# battery_buzzer.net
KiCad netlist of a schematic drawn in EAGLE
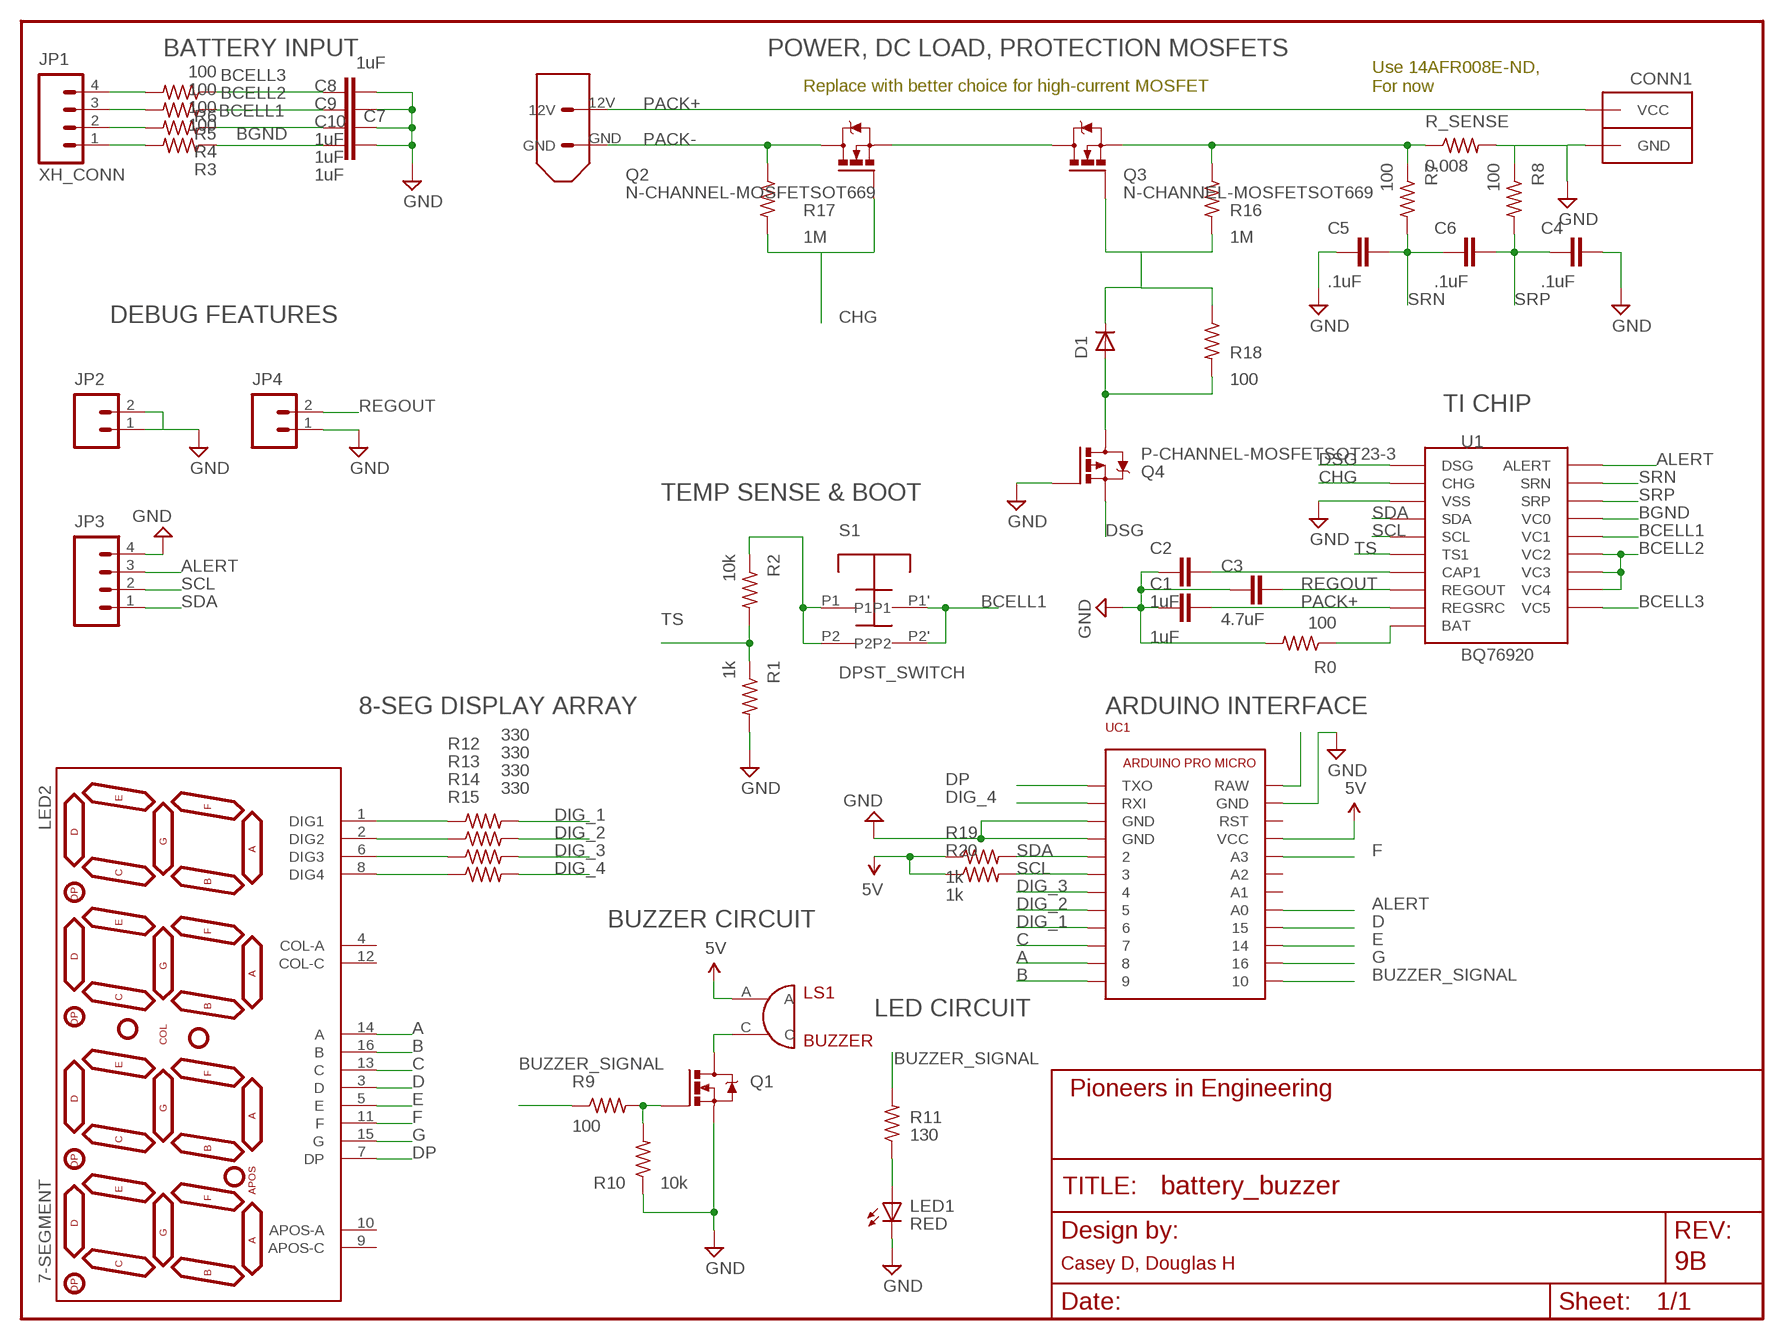
[diagram p0: schematic, sheet 1]

(export (version "E")
  (design (tool "Eeschema 10.0.6"))
  (components
    (comp (ref "C1")
      (value "1uF")
      (footprint "eagle-import:0603-CAP")
      (libsource (lib "eagle-import") (part "CAP0603-CAP"))
    )
    (comp (ref "C2")
      (value "1uF")
      (footprint "eagle-import:0603-CAP")
      (libsource (lib "eagle-import") (part "CAP0603-CAP"))
    )
    (comp (ref "C3")
      (value "4.7uF")
      (footprint "eagle-import:0603-CAP")
      (libsource (lib "eagle-import") (part "CAP0603-CAP"))
    )
    (comp (ref "C4")
      (value ".1uF")
      (footprint "eagle-import:0603-CAP")
      (libsource (lib "eagle-import") (part "CAP0603-CAP"))
    )
    (comp (ref "C5")
      (value ".1uF")
      (footprint "eagle-import:0603-CAP")
      (libsource (lib "eagle-import") (part "CAP0603-CAP"))
    )
    (comp (ref "C6")
      (value ".1uF")
      (footprint "eagle-import:0603-CAP")
      (libsource (lib "eagle-import") (part "CAP0603-CAP"))
    )
    (comp (ref "C7")
      (value "1uF")
      (footprint "eagle-import:0603-CAP")
      (libsource (lib "eagle-import") (part "CAP0603-CAP"))
    )
    (comp (ref "C8")
      (value "1uF")
      (footprint "eagle-import:0603-CAP")
      (libsource (lib "eagle-import") (part "CAP0603-CAP"))
    )
    (comp (ref "C9")
      (value "1uF")
      (footprint "eagle-import:0603-CAP")
      (libsource (lib "eagle-import") (part "CAP0603-CAP"))
    )
    (comp (ref "C10")
      (value "1uF")
      (footprint "eagle-import:0603-CAP")
      (libsource (lib "eagle-import") (part "CAP0603-CAP"))
    )
    (comp (ref "CONN1")
      (value "ANDERSONVERTICAL")
      (footprint "eagle-import:ANDERSON_VERTICAL")
      (libsource (lib "eagle-import") (part "ANDERSONVERTICAL"))
    )
    (comp (ref "D1")
      (value "DIODESOD-323")
      (footprint "eagle-import:SOD-323")
      (libsource (lib "eagle-import") (part "DIODESOD-323"))
    )
    (comp (ref "JP1")
      (value "XH_CONN")
      (footprint "eagle-import:XH_CONNECTOR_4POS_2.5MM")
      (libsource (lib "eagle-import") (part "XH_CONNECTOR_4POS"))
    )
    (comp (ref "JP2")
      (value "M02PTH")
      (footprint "eagle-import:1X02")
      (libsource (lib "eagle-import") (part "M02PTH"))
    )
    (comp (ref "JP3")
      (value "M04PTH")
      (footprint "eagle-import:1X04")
      (libsource (lib "eagle-import") (part "M04PTH"))
    )
    (comp (ref "JP4")
      (value "M02PTH")
      (footprint "eagle-import:1X02")
      (libsource (lib "eagle-import") (part "M02PTH"))
    )
    (comp (ref "LED1")
      (value "RED")
      (footprint "eagle-import:LED-0805")
      (libsource (lib "eagle-import") (part "LED0805"))
    )
    (comp (ref "LED2")
      (value "7-SEGMENT")
      (footprint "eagle-import:7-SEGMENT-4DIGIT-YOUNGSUN")
      (libsource (lib "eagle-import") (part "7-SEGMENT-4DIGIT-YOUNGSUN"))
    )
    (comp (ref "LS1")
      (value "BUZZER")
      (footprint "eagle-import:BUZZER_MAGNETIC_5V_12MM_RADIAL")
      (libsource (lib "eagle-import") (part "BUZZER"))
    )
    (comp (ref "Q1")
      (value "IRFML8244")
      (footprint "eagle-import:SOT23-3")
      (libsource (lib "eagle-import") (part "N-CHANNEL-MOSFETSOT23-3"))
    )
    (comp (ref "Q2")
      (value "N-CHANNEL-MOSFETSOT669")
      (footprint "eagle-import:SOT669")
      (libsource (lib "eagle-import") (part "N-CHANNEL-MOSFETSOT669"))
    )
    (comp (ref "Q3")
      (value "N-CHANNEL-MOSFETSOT669")
      (footprint "eagle-import:SOT669")
      (libsource (lib "eagle-import") (part "N-CHANNEL-MOSFETSOT669"))
    )
    (comp (ref "Q4")
      (value "P-CHANNEL-MOSFETSOT23-3")
      (footprint "eagle-import:SOT23-3")
      (libsource (lib "eagle-import") (part "P-CHANNEL-MOSFETSOT23-3"))
    )
    (comp (ref "R0")
      (value "100")
      (footprint "eagle-import:R0603")
      (libsource (lib "eagle-import") (part "R-US_R0603"))
    )
    (comp (ref "R1")
      (value "1k")
      (footprint "eagle-import:R0603")
      (libsource (lib "eagle-import") (part "R-US_R0603"))
    )
    (comp (ref "R2")
      (value "10k")
      (footprint "eagle-import:R0603")
      (libsource (lib "eagle-import") (part "R-US_R0603"))
    )
    (comp (ref "R3")
      (value "100")
      (footprint "eagle-import:R0603")
      (libsource (lib "eagle-import") (part "R-US_R0603"))
    )
    (comp (ref "R4")
      (value "100")
      (footprint "eagle-import:R0603")
      (libsource (lib "eagle-import") (part "R-US_R0603"))
    )
    (comp (ref "R5")
      (value "100")
      (footprint "eagle-import:R0603")
      (libsource (lib "eagle-import") (part "R-US_R0603"))
    )
    (comp (ref "R6")
      (value "100")
      (footprint "eagle-import:R0603")
      (libsource (lib "eagle-import") (part "R-US_R0603"))
    )
    (comp (ref "R7")
      (value "100")
      (footprint "eagle-import:R0603")
      (libsource (lib "eagle-import") (part "R-US_R0603"))
    )
    (comp (ref "R8")
      (value "100")
      (footprint "eagle-import:R0603")
      (libsource (lib "eagle-import") (part "R-US_R0603"))
    )
    (comp (ref "R9")
      (value "100")
      (footprint "eagle-import:R0603")
      (libsource (lib "eagle-import") (part "R-US_R0603"))
    )
    (comp (ref "R10")
      (value "10k")
      (footprint "eagle-import:R0603")
      (libsource (lib "eagle-import") (part "R-US_R0603"))
    )
    (comp (ref "R11")
      (value "130")
      (footprint "eagle-import:R0603")
      (libsource (lib "eagle-import") (part "R-US_R0603"))
    )
    (comp (ref "R12")
      (value "330")
      (footprint "eagle-import:R0603")
      (libsource (lib "eagle-import") (part "R-US_R0603"))
    )
    (comp (ref "R13")
      (value "330")
      (footprint "eagle-import:R0603")
      (libsource (lib "eagle-import") (part "R-US_R0603"))
    )
    (comp (ref "R14")
      (value "330")
      (footprint "eagle-import:R0603")
      (libsource (lib "eagle-import") (part "R-US_R0603"))
    )
    (comp (ref "R15")
      (value "330")
      (footprint "eagle-import:R0603")
      (libsource (lib "eagle-import") (part "R-US_R0603"))
    )
    (comp (ref "R16")
      (value "1M")
      (footprint "eagle-import:R0603")
      (libsource (lib "eagle-import") (part "R-US_R0603"))
    )
    (comp (ref "R17")
      (value "1M")
      (footprint "eagle-import:R0603")
      (libsource (lib "eagle-import") (part "R-US_R0603"))
    )
    (comp (ref "R18")
      (value "100")
      (footprint "eagle-import:R0603")
      (libsource (lib "eagle-import") (part "R-US_R0603"))
    )
    (comp (ref "R19")
      (value "1k")
      (footprint "eagle-import:R0603")
      (libsource (lib "eagle-import") (part "R-US_R0603"))
    )
    (comp (ref "R20")
      (value "1k")
      (footprint "eagle-import:R0603")
      (libsource (lib "eagle-import") (part "R-US_R0603"))
    )
    (comp (ref "R_SENSE")
      (value "0.008")
      (footprint "eagle-import:V235_17")
      (libsource (lib "eagle-import") (part "R-US_V235/17"))
    )
    (comp (ref "S1")
      (value "DPST_SWITCH")
      (footprint "eagle-import:C&K_SWITCH")
      (libsource (lib "eagle-import") (part "DPST_SWITCH"))
    )
    (comp (ref "U$1")
      (value "XT60CONNECTOR")
      (footprint "eagle-import:XT60CONNECTOR")
      (fields (field (name "PARTNUMBER") "PRT-10474 "))
      (libsource (lib "eagle-import") (part "XT60CONNECTOR"))
    )
    (comp (ref "U1")
      (value "BQ76920")
      (footprint "eagle-import:20-TSSOP")
      (libsource (lib "eagle-import") (part "BQ76920"))
    )
    (comp (ref "UC1")
      (value "ARDUINO_PRO_MICRO")
      (footprint "eagle-import:ARDUINO_PRO_MICRO")
      (libsource (lib "eagle-import") (part "ARDUINO_PRO_MICRO"))
    )
  )
  (nets
    (net (code "1") (name "/A") (class "Default")
      (node (ref "LED2") (pin "14") (pinfunction "A_14") (pintype "bidirectional"))
      (node (ref "UC1") (pin "8") (pinfunction "8_8") (pintype "bidirectional"))
    )
    (net (code "2") (name "/ALERT") (class "Default")
      (node (ref "JP3") (pin "3") (pinfunction "3_3") (pintype "passive"))
      (node (ref "U1") (pin "P$20") (pinfunction "ALERT_P$20") (pintype "bidirectional"))
      (node (ref "UC1") (pin "A0") (pinfunction "A0_A0") (pintype "bidirectional"))
    )
    (net (code "3") (name "/B") (class "Default")
      (node (ref "LED2") (pin "16") (pinfunction "B_16") (pintype "bidirectional"))
      (node (ref "UC1") (pin "9") (pinfunction "9_9") (pintype "bidirectional"))
    )
    (net (code "4") (name "/BCELL1") (class "Default")
      (node (ref "C9") (pin "1") (pinfunction "1_1") (pintype "passive"))
      (node (ref "R4") (pin "1") (pinfunction "1_1") (pintype "passive"))
      (node (ref "S1") (pin "P1'") (pinfunction "P1'_P1'") (pintype "bidirectional"))
      (node (ref "S1") (pin "P2'") (pinfunction "P2'_P2'") (pintype "bidirectional"))
      (node (ref "U1") (pin "P$16") (pinfunction "VC1_P$16") (pintype "bidirectional"))
    )
    (net (code "5") (name "/BCELL2") (class "Default")
      (node (ref "C8") (pin "1") (pinfunction "1_1") (pintype "passive"))
      (node (ref "R5") (pin "1") (pinfunction "1_1") (pintype "passive"))
      (node (ref "U1") (pin "P$13") (pinfunction "VC4_P$13") (pintype "bidirectional"))
      (node (ref "U1") (pin "P$14") (pinfunction "VC3_P$14") (pintype "bidirectional"))
      (node (ref "U1") (pin "P$15") (pinfunction "VC2_P$15") (pintype "bidirectional"))
    )
    (net (code "6") (name "/BCELL3") (class "Default")
      (node (ref "C7") (pin "2") (pinfunction "2_2") (pintype "passive"))
      (node (ref "R6") (pin "1") (pinfunction "1_1") (pintype "passive"))
      (node (ref "U1") (pin "P$12") (pinfunction "VC5_P$12") (pintype "bidirectional"))
    )
    (net (code "7") (name "/BGND") (class "Default")
      (node (ref "C10") (pin "1") (pinfunction "1_1") (pintype "passive"))
      (node (ref "R3") (pin "1") (pinfunction "1_1") (pintype "passive"))
      (node (ref "U1") (pin "P$17") (pinfunction "VC0_P$17") (pintype "bidirectional"))
    )
    (net (code "8") (name "/BUZZER_SIGNAL") (class "Default")
      (node (ref "R11") (pin "2") (pinfunction "2_2") (pintype "passive"))
      (node (ref "R9") (pin "1") (pinfunction "1_1") (pintype "passive"))
      (node (ref "UC1") (pin "10") (pinfunction "10_10") (pintype "bidirectional"))
    )
    (net (code "9") (name "/C") (class "Default")
      (node (ref "LED2") (pin "13") (pinfunction "C_13") (pintype "bidirectional"))
      (node (ref "UC1") (pin "7") (pinfunction "7_7") (pintype "bidirectional"))
    )
    (net (code "10") (name "/CHG") (class "Default")
      (node (ref "Q2") (pin "4") (pinfunction "G_4") (pintype "passive"))
      (node (ref "R17") (pin "2") (pinfunction "2_2") (pintype "passive"))
      (node (ref "U1") (pin "P$2") (pinfunction "CHG_P$2") (pintype "bidirectional"))
    )
    (net (code "11") (name "/D") (class "Default")
      (node (ref "LED2") (pin "3") (pinfunction "D_3") (pintype "bidirectional"))
      (node (ref "UC1") (pin "15") (pinfunction "15_15") (pintype "bidirectional"))
    )
    (net (code "12") (name "/DIG_1") (class "Default")
      (node (ref "R12") (pin "2") (pinfunction "2_2") (pintype "passive"))
      (node (ref "UC1") (pin "6") (pinfunction "6_6") (pintype "bidirectional"))
    )
    (net (code "13") (name "/DIG_2") (class "Default")
      (node (ref "R13") (pin "2") (pinfunction "2_2") (pintype "passive"))
      (node (ref "UC1") (pin "5") (pinfunction "5_5") (pintype "bidirectional"))
    )
    (net (code "14") (name "/DIG_3") (class "Default")
      (node (ref "R14") (pin "2") (pinfunction "2_2") (pintype "passive"))
      (node (ref "UC1") (pin "4") (pinfunction "4_4") (pintype "bidirectional"))
    )
    (net (code "15") (name "/DIG_4") (class "Default")
      (node (ref "R15") (pin "2") (pinfunction "2_2") (pintype "passive"))
      (node (ref "UC1") (pin "RXI") (pinfunction "RXI_RXI") (pintype "bidirectional"))
    )
    (net (code "16") (name "/DP") (class "Default")
      (node (ref "LED2") (pin "7") (pinfunction "DP_7") (pintype "bidirectional"))
      (node (ref "UC1") (pin "TXO") (pinfunction "TXO_TXO") (pintype "bidirectional"))
    )
    (net (code "17") (name "/DSG") (class "Default")
      (node (ref "Q4") (pin "2") (pinfunction "S_2") (pintype "passive"))
      (node (ref "U1") (pin "P$1") (pinfunction "DSG_P$1") (pintype "bidirectional"))
    )
    (net (code "18") (name "/E") (class "Default")
      (node (ref "LED2") (pin "5") (pinfunction "E_5") (pintype "bidirectional"))
      (node (ref "UC1") (pin "14") (pinfunction "14_14") (pintype "bidirectional"))
    )
    (net (code "19") (name "/F") (class "Default")
      (node (ref "LED2") (pin "11") (pinfunction "F_11") (pintype "bidirectional"))
      (node (ref "UC1") (pin "A3") (pinfunction "A3_A3") (pintype "bidirectional"))
    )
    (net (code "20") (name "/G") (class "Default")
      (node (ref "LED2") (pin "15") (pinfunction "G_15") (pintype "bidirectional"))
      (node (ref "UC1") (pin "16") (pinfunction "16_16") (pintype "bidirectional"))
    )
    (net (code "21") (name "/PACK+") (class "Default")
      (node (ref "C1") (pin "2") (pinfunction "2_2") (pintype "passive"))
      (node (ref "CONN1") (pin "PIN2") (pinfunction "VCC_PIN2") (pintype "bidirectional"))
      (node (ref "U$1") (pin "12V") (pinfunction "12V_12V") (pintype "bidirectional"))
      (node (ref "U1") (pin "P$9") (pinfunction "REGSRC_P$9") (pintype "bidirectional"))
    )
    (net (code "22") (name "/PACK-") (class "Default")
      (node (ref "Q2") (pin "MB") (pinfunction "D_MB") (pintype "passive"))
      (node (ref "R17") (pin "1") (pinfunction "1_1") (pintype "passive"))
      (node (ref "U$1") (pin "GND") (pinfunction "GND_GND") (pintype "bidirectional"))
    )
    (net (code "23") (name "/REGOUT") (class "Default")
      (node (ref "C3") (pin "2") (pinfunction "2_2") (pintype "passive"))
      (node (ref "JP4") (pin "2") (pinfunction "2_2") (pintype "passive"))
      (node (ref "U1") (pin "P$8") (pinfunction "REGOUT_P$8") (pintype "bidirectional"))
    )
    (net (code "24") (name "/SCL") (class "Default")
      (node (ref "JP3") (pin "2") (pinfunction "2_2") (pintype "passive"))
      (node (ref "R20") (pin "2") (pinfunction "2_2") (pintype "passive"))
      (node (ref "U1") (pin "P$5") (pinfunction "SCL_P$5") (pintype "bidirectional"))
      (node (ref "UC1") (pin "3") (pinfunction "3_3") (pintype "bidirectional"))
    )
    (net (code "25") (name "/SDA") (class "Default")
      (node (ref "JP3") (pin "1") (pinfunction "1_1") (pintype "passive"))
      (node (ref "R19") (pin "2") (pinfunction "2_2") (pintype "passive"))
      (node (ref "U1") (pin "P$4") (pinfunction "SDA_P$4") (pintype "bidirectional"))
      (node (ref "UC1") (pin "2") (pinfunction "2_2") (pintype "bidirectional"))
    )
    (net (code "26") (name "/SRN") (class "Default")
      (node (ref "C5") (pin "2") (pinfunction "2_2") (pintype "passive"))
      (node (ref "C6") (pin "1") (pinfunction "1_1") (pintype "passive"))
      (node (ref "R7") (pin "2") (pinfunction "2_2") (pintype "passive"))
      (node (ref "U1") (pin "P$19") (pinfunction "SRN_P$19") (pintype "bidirectional"))
    )
    (net (code "27") (name "/SRP") (class "Default")
      (node (ref "C4") (pin "1") (pinfunction "1_1") (pintype "passive"))
      (node (ref "C6") (pin "2") (pinfunction "2_2") (pintype "passive"))
      (node (ref "R8") (pin "2") (pinfunction "2_2") (pintype "passive"))
      (node (ref "U1") (pin "P$18") (pinfunction "SRP_P$18") (pintype "bidirectional"))
    )
    (net (code "28") (name "/TS") (class "Default")
      (node (ref "R1") (pin "1") (pinfunction "1_1") (pintype "passive"))
      (node (ref "R2") (pin "2") (pinfunction "2_2") (pintype "passive"))
      (node (ref "U1") (pin "P$6") (pinfunction "TS1_P$6") (pintype "bidirectional"))
    )
    (net (code "29") (name "5V") (class "Default")
      (node (ref "LS1") (pin "A") (pinfunction "A_A") (pintype "bidirectional"))
      (node (ref "R19") (pin "1") (pinfunction "1_1") (pintype "passive"))
      (node (ref "R20") (pin "1") (pinfunction "1_1") (pintype "passive"))
      (node (ref "UC1") (pin "VCC") (pinfunction "VCC_VCC") (pintype "bidirectional"))
    )
    (net (code "30") (name "GND") (class "Default")
      (node (ref "C1") (pin "1") (pinfunction "1_1") (pintype "passive"))
      (node (ref "C10") (pin "2") (pinfunction "2_2") (pintype "passive"))
      (node (ref "C2") (pin "1") (pinfunction "1_1") (pintype "passive"))
      (node (ref "C3") (pin "1") (pinfunction "1_1") (pintype "passive"))
      (node (ref "C4") (pin "2") (pinfunction "2_2") (pintype "passive"))
      (node (ref "C5") (pin "1") (pinfunction "1_1") (pintype "passive"))
      (node (ref "C7") (pin "1") (pinfunction "1_1") (pintype "passive"))
      (node (ref "C8") (pin "2") (pinfunction "2_2") (pintype "passive"))
      (node (ref "C9") (pin "2") (pinfunction "2_2") (pintype "passive"))
      (node (ref "CONN1") (pin "PIN1") (pinfunction "GND_PIN1") (pintype "bidirectional"))
      (node (ref "JP2") (pin "1") (pinfunction "1_1") (pintype "passive"))
      (node (ref "JP2") (pin "2") (pinfunction "2_2") (pintype "passive"))
      (node (ref "JP3") (pin "4") (pinfunction "4_4") (pintype "passive"))
      (node (ref "JP4") (pin "1") (pinfunction "1_1") (pintype "passive"))
      (node (ref "LED1") (pin "C") (pinfunction "C_C") (pintype "passive"))
      (node (ref "Q1") (pin "2") (pinfunction "S_2") (pintype "passive"))
      (node (ref "Q4") (pin "1") (pinfunction "G_1") (pintype "passive"))
      (node (ref "R0") (pin "2") (pinfunction "2_2") (pintype "passive"))
      (node (ref "R1") (pin "2") (pinfunction "2_2") (pintype "passive"))
      (node (ref "R10") (pin "1") (pinfunction "1_1") (pintype "passive"))
      (node (ref "R8") (pin "1") (pinfunction "1_1") (pintype "passive"))
      (node (ref "R_SENSE") (pin "2") (pinfunction "2_2") (pintype "passive"))
      (node (ref "U1") (pin "P$3") (pinfunction "VSS_P$3") (pintype "bidirectional"))
      (node (ref "UC1") (pin "GND@0") (pinfunction "GND_GND@0") (pintype "bidirectional"))
      (node (ref "UC1") (pin "GND@1") (pinfunction "GND_GND@1") (pintype "bidirectional"))
      (node (ref "UC1") (pin "GND@2") (pinfunction "GND_GND@2") (pintype "bidirectional"))
    )
    (net (code "31") (name "Net-(D1-A)") (class "Default")
      (node (ref "D1") (pin "1") (pinfunction "A_1") (pintype "passive"))
      (node (ref "Q4") (pin "3") (pinfunction "D_3") (pintype "passive"))
      (node (ref "R18") (pin "2") (pinfunction "2_2") (pintype "passive"))
    )
    (net (code "32") (name "Net-(D1-C)") (class "Default")
      (node (ref "D1") (pin "2") (pinfunction "C_2") (pintype "passive"))
      (node (ref "Q3") (pin "4") (pinfunction "G_4") (pintype "passive"))
      (node (ref "R16") (pin "2") (pinfunction "2_2") (pintype "passive"))
      (node (ref "R18") (pin "1") (pinfunction "1_1") (pintype "passive"))
    )
    (net (code "33") (name "Net-(JP1-Pad1)") (class "Default")
      (node (ref "JP1") (pin "1") (pinfunction "1_1") (pintype "passive"))
      (node (ref "R3") (pin "2") (pinfunction "2_2") (pintype "passive"))
    )
    (net (code "34") (name "Net-(JP1-Pad2)") (class "Default")
      (node (ref "JP1") (pin "2") (pinfunction "2_2") (pintype "passive"))
      (node (ref "R4") (pin "2") (pinfunction "2_2") (pintype "passive"))
    )
    (net (code "35") (name "Net-(JP1-Pad3)") (class "Default")
      (node (ref "JP1") (pin "3") (pinfunction "3_3") (pintype "passive"))
      (node (ref "R5") (pin "2") (pinfunction "2_2") (pintype "passive"))
    )
    (net (code "36") (name "Net-(JP1-Pad4)") (class "Default")
      (node (ref "JP1") (pin "4") (pinfunction "4_4") (pintype "passive"))
      (node (ref "R6") (pin "2") (pinfunction "2_2") (pintype "passive"))
    )
    (net (code "37") (name "Net-(LED1-PadA)") (class "Default")
      (node (ref "LED1") (pin "A") (pinfunction "A_A") (pintype "passive"))
      (node (ref "R11") (pin "1") (pinfunction "1_1") (pintype "passive"))
    )
    (net (code "38") (name "Net-(LED2-DIG1)") (class "Default")
      (node (ref "LED2") (pin "1") (pinfunction "DIG1_1") (pintype "bidirectional"))
      (node (ref "R12") (pin "1") (pinfunction "1_1") (pintype "passive"))
    )
    (net (code "39") (name "Net-(LED2-DIG2)") (class "Default")
      (node (ref "LED2") (pin "2") (pinfunction "DIG2_2") (pintype "bidirectional"))
      (node (ref "R13") (pin "1") (pinfunction "1_1") (pintype "passive"))
    )
    (net (code "40") (name "Net-(LED2-DIG3)") (class "Default")
      (node (ref "LED2") (pin "6") (pinfunction "DIG3_6") (pintype "bidirectional"))
      (node (ref "R14") (pin "1") (pinfunction "1_1") (pintype "passive"))
    )
    (net (code "41") (name "Net-(LED2-DIG4)") (class "Default")
      (node (ref "LED2") (pin "8") (pinfunction "DIG4_8") (pintype "bidirectional"))
      (node (ref "R15") (pin "1") (pinfunction "1_1") (pintype "passive"))
    )
    (net (code "42") (name "Net-(Q1-D)") (class "Default")
      (node (ref "LS1") (pin "C") (pinfunction "C_C") (pintype "bidirectional"))
      (node (ref "Q1") (pin "3") (pinfunction "D_3") (pintype "passive"))
    )
    (net (code "43") (name "Net-(Q1-G)") (class "Default")
      (node (ref "Q1") (pin "1") (pinfunction "G_1") (pintype "passive"))
      (node (ref "R10") (pin "2") (pinfunction "2_2") (pintype "passive"))
      (node (ref "R9") (pin "2") (pinfunction "2_2") (pintype "passive"))
    )
    (net (code "44") (name "Net-(Q3-D)") (class "Default")
      (node (ref "Q2") (pin "1") (pinfunction "S_1") (pintype "passive"))
      (node (ref "Q2") (pin "2") (pinfunction "S_2") (pintype "passive"))
      (node (ref "Q2") (pin "3") (pinfunction "S_3") (pintype "passive"))
      (node (ref "Q3") (pin "MB") (pinfunction "D_MB") (pintype "passive"))
    )
    (net (code "45") (name "Net-(Q3-S-Pad1)") (class "Default")
      (node (ref "Q3") (pin "1") (pinfunction "S_1") (pintype "passive"))
      (node (ref "Q3") (pin "2") (pinfunction "S_2") (pintype "passive"))
      (node (ref "Q3") (pin "3") (pinfunction "S_3") (pintype "passive"))
      (node (ref "R16") (pin "1") (pinfunction "1_1") (pintype "passive"))
      (node (ref "R7") (pin "1") (pinfunction "1_1") (pintype "passive"))
      (node (ref "R_SENSE") (pin "1") (pinfunction "1_1") (pintype "passive"))
    )
    (net (code "46") (name "Net-(R2-Pad1)") (class "Default")
      (node (ref "R2") (pin "1") (pinfunction "1_1") (pintype "passive"))
      (node (ref "S1") (pin "P1") (pinfunction "P1_P1") (pintype "bidirectional"))
      (node (ref "S1") (pin "P2") (pinfunction "P2_P2") (pintype "bidirectional"))
    )
    (net (code "47") (name "Net-(U1-BAT)") (class "Default")
      (node (ref "R0") (pin "1") (pinfunction "1_1") (pintype "passive"))
      (node (ref "U1") (pin "P$10") (pinfunction "BAT_P$10") (pintype "bidirectional"))
    )
    (net (code "48") (name "Net-(U1-CAP1)") (class "Default")
      (node (ref "C2") (pin "2") (pinfunction "2_2") (pintype "passive"))
      (node (ref "U1") (pin "P$7") (pinfunction "CAP1_P$7") (pintype "bidirectional"))
    )
    (net (code "49") (name "unconnected-(LED2-APOS-A-Pad10)") (class "Default")
      (node (ref "LED2") (pin "10") (pinfunction "APOS-A_10") (pintype "bidirectional"))
    )
    (net (code "50") (name "unconnected-(LED2-APOS-C-Pad9)") (class "Default")
      (node (ref "LED2") (pin "9") (pinfunction "APOS-C_9") (pintype "bidirectional"))
    )
    (net (code "51") (name "unconnected-(LED2-COL-A-Pad4)") (class "Default")
      (node (ref "LED2") (pin "4") (pinfunction "COL-A_4") (pintype "bidirectional"))
    )
    (net (code "52") (name "unconnected-(LED2-COL-C-Pad12)") (class "Default")
      (node (ref "LED2") (pin "12") (pinfunction "COL-C_12") (pintype "bidirectional"))
    )
    (net (code "53") (name "unconnected-(UC1-PadA1)") (class "Default")
      (node (ref "UC1") (pin "A1") (pinfunction "A1_A1") (pintype "bidirectional"))
    )
    (net (code "54") (name "unconnected-(UC1-PadA2)") (class "Default")
      (node (ref "UC1") (pin "A2") (pinfunction "A2_A2") (pintype "bidirectional"))
    )
    (net (code "55") (name "unconnected-(UC1-PadRAW)") (class "Default")
      (node (ref "UC1") (pin "RAW") (pinfunction "RAW_RAW") (pintype "bidirectional"))
    )
    (net (code "56") (name "unconnected-(UC1-PadRST)") (class "Default")
      (node (ref "UC1") (pin "RST") (pinfunction "RST_RST") (pintype "bidirectional"))
    )
  )
)
